# pi-zigbee-poe-rtc.net
KiCad netlist of a schematic drawn in EAGLE
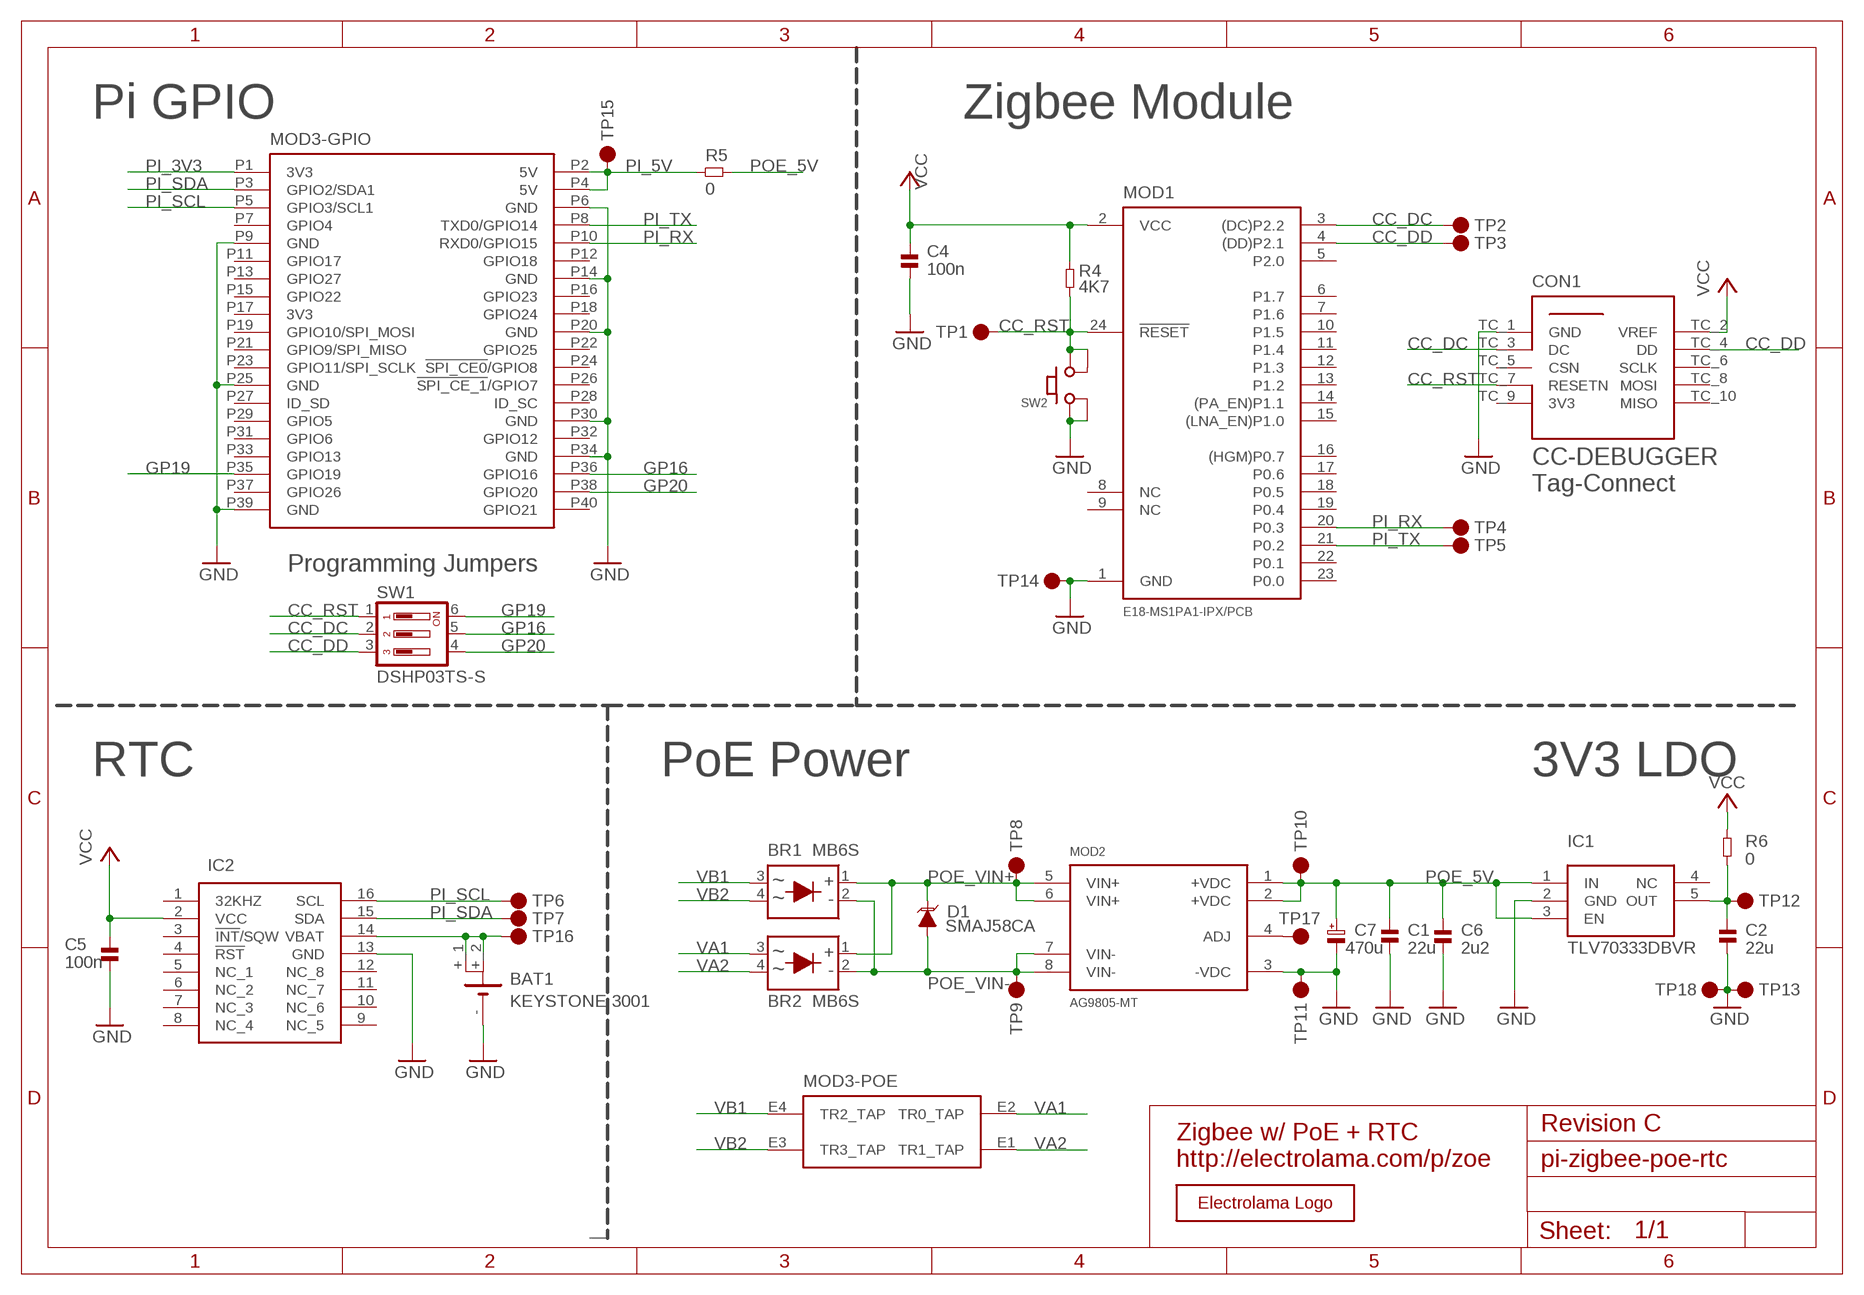
[diagram p0: schematic, sheet 1]

(export (version "E")
  (design (tool "Eeschema 10.0.6"))
  (components
    (comp (ref "BAT1")
      (value "KEYSTONE 3001")
      (footprint "eagle-import:KEYSTONE_3001")
      (libsource (lib "eagle-import") (part "BATTERY"))
    )
    (comp (ref "BR1")
      (value "MB6S")
      (footprint "eagle-import:SOP254P665X270-4N")
      (fields
        (field (name "MANUFACTURER_PART_NUMBER") "MB6S-TP")
        (field (name "MOUSER_PART_NUMBER") "833-MB6S-TP")
      )
      (libsource (lib "eagle-import") (part "DIODE-RECTIFIER-MB6S"))
    )
    (comp (ref "BR2")
      (value "MB6S")
      (footprint "eagle-import:SOP254P665X270-4N")
      (fields
        (field (name "MANUFACTURER_PART_NUMBER") "MB6S-TP")
        (field (name "MOUSER_PART_NUMBER") "833-MB6S-TP")
      )
      (libsource (lib "eagle-import") (part "DIODE-RECTIFIER-MB6S"))
    )
    (comp (ref "C1")
      (value "22u")
      (footprint "eagle-import:_PKG_C_0805")
      (libsource (lib "eagle-import") (part "CAP-0805"))
    )
    (comp (ref "C2")
      (value "22u")
      (footprint "eagle-import:_PKG_C_0805")
      (libsource (lib "eagle-import") (part "CAP-0805"))
    )
    (comp (ref "C4")
      (value "100n")
      (footprint "eagle-import:_PKG_C_0603")
      (libsource (lib "eagle-import") (part "CAP-0603"))
    )
    (comp (ref "C5")
      (value "100n")
      (footprint "eagle-import:_PKG_C_0603")
      (libsource (lib "eagle-import") (part "CAP-0603"))
    )
    (comp (ref "C6")
      (value "2u2")
      (footprint "eagle-import:_PKG_C_0603")
      (libsource (lib "eagle-import") (part "CAP-0603"))
    )
    (comp (ref "C7")
      (value "470u")
      (footprint "eagle-import:_CAP_ELCO_D8_L10.5")
      (libsource (lib "eagle-import") (part "CAP-POL-ELCO-D8-L10.5"))
    )
    (comp (ref "CON1")
      (value "TC2050-IDC-NL_CC-DEBUGGER")
      (footprint "eagle-import:TC2050-IDC-NL")
      (libsource (lib "eagle-import") (part "TC2050-IDC-NL_CC-DEBUGGER"))
    )
    (comp (ref "D1")
      (value "SMAJ58CA")
      (footprint "eagle-import:DIOM5126X250N-NOPOL")
      (libsource (lib "eagle-import") (part "DIODE-TVS-SMAJ58CA"))
    )
    (comp (ref "IC1")
      (value "TLV70333DBVR")
      (footprint "eagle-import:SOT95P280X145-5N")
      (fields (field (name "MOUSER_PART_NUMBER") "595-TLV70333DBVR"))
      (libsource (lib "eagle-import") (part "LDO-TLV70333DBVR"))
    )
    (comp (ref "IC2")
      (value "RTC-DS3231SN#")
      (footprint "eagle-import:SOIC127P1032X265-16N")
      (fields
        (field (name "MANUFACTURER_PART_NUMBER") "DS3231SN#")
        (field (name "MOUSER_PART_NUMBER") "700-DS3231SN#")
        (field (name "RS_PART_NUMBER") "1897251")
      )
      (libsource (lib "eagle-import") (part "RTC-DS3231SN#"))
    )
    (comp (ref "MOD1")
      (value "E18-MS1PA1-IPX/PCB")
      (footprint "eagle-import:EBYTE-E18-MS1PA1")
      (libsource (lib "eagle-import") (part "EBYTE-E18-MS1PA1"))
    )
    (comp (ref "MOD2")
      (value "AG9805-MT")
      (footprint "eagle-import:SILVERTEL_AG9800M")
      (libsource (lib "eagle-import") (part "SILVERTEL_AG9800M"))
    )
    (comp (ref "MOD3")
      (value "RPI-HAT-FULL")
      (footprint "eagle-import:RPI-HAT-FULL")
      (libsource (lib "eagle-import") (part "RPI-HAT-FULL"))
    )
    (comp (ref "R4")
      (value "4K7")
      (footprint "eagle-import:_PKG_C_0603")
      (libsource (lib "eagle-import") (part "RES-0603"))
    )
    (comp (ref "R5")
      (value "0")
      (footprint "eagle-import:TP_DUAL_1206")
      (libsource (lib "eagle-import") (part "TP_DUAL_1206"))
    )
    (comp (ref "R6")
      (value "0")
      (footprint "eagle-import:TP_DUAL_1206")
      (libsource (lib "eagle-import") (part "TP_DUAL_1206"))
    )
    (comp (ref "SW1")
      (value "DSHP03TS-S")
      (footprint "eagle-import:DSHP03TS-S")
      (libsource (lib "eagle-import") (part "SWITCH-DIP03-SMD"))
    )
    (comp (ref "SW2")
      (value "SPNO-XKB-TS-1187A")
      (footprint "eagle-import:XKB-TS-1187A")
      (libsource (lib "eagle-import") (part "SPNO-XKB-TS-1187A"))
    )
    (comp (ref "TP1")
      (value "TP")
      (footprint "eagle-import:TP_DOT")
      (libsource (lib "eagle-import") (part "TP"))
    )
    (comp (ref "TP2")
      (value "TP")
      (footprint "eagle-import:TP_DOT")
      (libsource (lib "eagle-import") (part "TP"))
    )
    (comp (ref "TP3")
      (value "TP")
      (footprint "eagle-import:TP_DOT")
      (libsource (lib "eagle-import") (part "TP"))
    )
    (comp (ref "TP4")
      (value "TP")
      (footprint "eagle-import:TP_DOT")
      (libsource (lib "eagle-import") (part "TP"))
    )
    (comp (ref "TP5")
      (value "TP")
      (footprint "eagle-import:TP_DOT")
      (libsource (lib "eagle-import") (part "TP"))
    )
    (comp (ref "TP6")
      (value "TP")
      (footprint "eagle-import:TP_DOT")
      (libsource (lib "eagle-import") (part "TP"))
    )
    (comp (ref "TP7")
      (value "TP")
      (footprint "eagle-import:TP_DOT")
      (libsource (lib "eagle-import") (part "TP"))
    )
    (comp (ref "TP8")
      (value "TP")
      (footprint "eagle-import:TP_DOT")
      (libsource (lib "eagle-import") (part "TP"))
    )
    (comp (ref "TP9")
      (value "TP")
      (footprint "eagle-import:TP_DOT")
      (libsource (lib "eagle-import") (part "TP"))
    )
    (comp (ref "TP10")
      (value "TP")
      (footprint "eagle-import:TP_DOT")
      (libsource (lib "eagle-import") (part "TP"))
    )
    (comp (ref "TP11")
      (value "TP")
      (footprint "eagle-import:TP_DOT")
      (libsource (lib "eagle-import") (part "TP"))
    )
    (comp (ref "TP12")
      (value "TP")
      (footprint "eagle-import:TP_DOT")
      (libsource (lib "eagle-import") (part "TP"))
    )
    (comp (ref "TP13")
      (value "TP")
      (footprint "eagle-import:TP_DOT")
      (libsource (lib "eagle-import") (part "TP"))
    )
    (comp (ref "TP14")
      (value "TP")
      (footprint "eagle-import:TP_DOT")
      (libsource (lib "eagle-import") (part "TP"))
    )
    (comp (ref "TP15")
      (value "TP")
      (footprint "eagle-import:TP_DOT")
      (libsource (lib "eagle-import") (part "TP"))
    )
    (comp (ref "TP16")
      (value "TP")
      (footprint "eagle-import:TP_DOT")
      (libsource (lib "eagle-import") (part "TP"))
    )
    (comp (ref "TP17")
      (value "TP")
      (footprint "eagle-import:TP_DOT")
      (libsource (lib "eagle-import") (part "TP"))
    )
    (comp (ref "TP18")
      (value "TP-HOOK")
      (footprint "eagle-import:TP_S2751-46R")
      (libsource (lib "eagle-import") (part "TP-HOOK"))
    )
    (comp (ref "U$1")
      (value "LOGO-ELECTROLAMA")
      (footprint "eagle-import:ELECTROLAMA")
      (libsource (lib "eagle-import") (part "LOGO-ELECTROLAMA"))
    )
  )
  (nets
    (net (code "1") (name "/CC_DC") (class "Default")
      (node (ref "CON1") (pin "TC_3") (pinfunction "DC_TC_3") (pintype "bidirectional"))
      (node (ref "MOD1") (pin "3") (pinfunction "(DC)P2.2_3") (pintype "bidirectional"))
      (node (ref "SW1") (pin "2") (pinfunction "2_2") (pintype "passive"))
      (node (ref "TP2") (pin "TP") (pinfunction "TP_TP") (pintype "bidirectional"))
    )
    (net (code "2") (name "/CC_DD") (class "Default")
      (node (ref "CON1") (pin "TC_4") (pinfunction "DD_TC_4") (pintype "bidirectional"))
      (node (ref "MOD1") (pin "4") (pinfunction "(DD)P2.1_4") (pintype "bidirectional"))
      (node (ref "SW1") (pin "3") (pinfunction "3_3") (pintype "passive"))
      (node (ref "TP3") (pin "TP") (pinfunction "TP_TP") (pintype "bidirectional"))
    )
    (net (code "3") (name "/CC_RST") (class "Default")
      (node (ref "CON1") (pin "TC_7") (pinfunction "RESETN_TC_7") (pintype "bidirectional"))
      (node (ref "MOD1") (pin "24") (pinfunction "~{RESET}_24") (pintype "input"))
      (node (ref "R4") (pin "1") (pinfunction "1_1") (pintype "passive"))
      (node (ref "SW1") (pin "1") (pinfunction "1_1") (pintype "passive"))
      (node (ref "SW2") (pin "C") (pinfunction "2_1_C") (pintype "bidirectional"))
      (node (ref "SW2") (pin "D") (pinfunction "2_2_D") (pintype "bidirectional"))
      (node (ref "TP1") (pin "TP") (pinfunction "TP_TP") (pintype "bidirectional"))
    )
    (net (code "4") (name "/GP16") (class "Default")
      (node (ref "MOD3") (pin "P36") (pinfunction "GPIO16_P36") (pintype "bidirectional"))
      (node (ref "SW1") (pin "5") (pinfunction "5_5") (pintype "passive"))
    )
    (net (code "5") (name "/GP19") (class "Default")
      (node (ref "MOD3") (pin "P35") (pinfunction "GPIO19_P35") (pintype "bidirectional"))
      (node (ref "SW1") (pin "6") (pinfunction "6_6") (pintype "passive"))
    )
    (net (code "6") (name "/GP20") (class "Default")
      (node (ref "MOD3") (pin "P38") (pinfunction "GPIO20_P38") (pintype "bidirectional"))
      (node (ref "SW1") (pin "4") (pinfunction "4_4") (pintype "passive"))
    )
    (net (code "7") (name "/PI_3V3") (class "Default")
      (node (ref "MOD3") (pin "P1") (pinfunction "3V3_P1") (pintype "bidirectional"))
    )
    (net (code "8") (name "/PI_5V") (class "Default")
      (node (ref "MOD3") (pin "P2") (pinfunction "5V_P2") (pintype "bidirectional"))
      (node (ref "MOD3") (pin "P4") (pinfunction "5V_P4") (pintype "bidirectional"))
      (node (ref "R5") (pin "1") (pinfunction "1_1") (pintype "passive"))
      (node (ref "TP15") (pin "TP") (pinfunction "TP_TP") (pintype "bidirectional"))
    )
    (net (code "9") (name "/PI_RX") (class "Default")
      (node (ref "MOD1") (pin "20") (pinfunction "P0.3_20") (pintype "bidirectional"))
      (node (ref "MOD3") (pin "P10") (pinfunction "RXD0/GPIO15_P10") (pintype "bidirectional"))
      (node (ref "TP4") (pin "TP") (pinfunction "TP_TP") (pintype "bidirectional"))
    )
    (net (code "10") (name "/PI_SCL") (class "Default")
      (node (ref "IC2") (pin "16") (pinfunction "SCL_16") (pintype "bidirectional"))
      (node (ref "MOD3") (pin "P5") (pinfunction "GPIO3/SCL1_P5") (pintype "bidirectional"))
      (node (ref "TP6") (pin "TP") (pinfunction "TP_TP") (pintype "bidirectional"))
    )
    (net (code "11") (name "/PI_SDA") (class "Default")
      (node (ref "IC2") (pin "15") (pinfunction "SDA_15") (pintype "bidirectional"))
      (node (ref "MOD3") (pin "P3") (pinfunction "GPIO2/SDA1_P3") (pintype "bidirectional"))
      (node (ref "TP7") (pin "TP") (pinfunction "TP_TP") (pintype "bidirectional"))
    )
    (net (code "12") (name "/PI_TX") (class "Default")
      (node (ref "MOD1") (pin "21") (pinfunction "P0.2_21") (pintype "bidirectional"))
      (node (ref "MOD3") (pin "P8") (pinfunction "TXD0/GPIO14_P8") (pintype "bidirectional"))
      (node (ref "TP5") (pin "TP") (pinfunction "TP_TP") (pintype "bidirectional"))
    )
    (net (code "13") (name "/POE_5V") (class "Default")
      (node (ref "C1") (pin "2") (pinfunction "2_2") (pintype "passive"))
      (node (ref "C6") (pin "1") (pinfunction "1_1") (pintype "passive"))
      (node (ref "C7") (pin "+") (pinfunction "+_+") (pintype "passive"))
      (node (ref "IC1") (pin "1") (pinfunction "IN_1") (pintype "bidirectional"))
      (node (ref "IC1") (pin "3") (pinfunction "EN_3") (pintype "bidirectional"))
      (node (ref "MOD2") (pin "1") (pinfunction "+VDC_1") (pintype "bidirectional"))
      (node (ref "MOD2") (pin "2") (pinfunction "+VDC_2") (pintype "bidirectional"))
      (node (ref "R5") (pin "2") (pinfunction "2_2") (pintype "passive"))
      (node (ref "TP10") (pin "TP") (pinfunction "TP_TP") (pintype "bidirectional"))
    )
    (net (code "14") (name "/POE_VIN+") (class "Default")
      (node (ref "BR1") (pin "1") (pinfunction "+_1") (pintype "bidirectional"))
      (node (ref "BR2") (pin "1") (pinfunction "+_1") (pintype "bidirectional"))
      (node (ref "D1") (pin "1") (pinfunction "C_1") (pintype "passive"))
      (node (ref "MOD2") (pin "5") (pinfunction "VIN+_5") (pintype "bidirectional"))
      (node (ref "MOD2") (pin "6") (pinfunction "VIN+_6") (pintype "bidirectional"))
      (node (ref "TP8") (pin "TP") (pinfunction "TP_TP") (pintype "bidirectional"))
    )
    (net (code "15") (name "/POE_VIN-") (class "Default")
      (node (ref "BR1") (pin "2") (pinfunction "-_2") (pintype "bidirectional"))
      (node (ref "BR2") (pin "2") (pinfunction "-_2") (pintype "bidirectional"))
      (node (ref "D1") (pin "2") (pinfunction "A_2") (pintype "passive"))
      (node (ref "MOD2") (pin "7") (pinfunction "VIN-_7") (pintype "bidirectional"))
      (node (ref "MOD2") (pin "8") (pinfunction "VIN-_8") (pintype "bidirectional"))
      (node (ref "TP9") (pin "TP") (pinfunction "TP_TP") (pintype "bidirectional"))
    )
    (net (code "16") (name "/VA1") (class "Default")
      (node (ref "BR2") (pin "3") (pinfunction "~_3") (pintype "bidirectional"))
      (node (ref "MOD3") (pin "E2") (pinfunction "TR0_TAP_E2") (pintype "bidirectional"))
    )
    (net (code "17") (name "/VA2") (class "Default")
      (node (ref "BR2") (pin "4") (pinfunction "~_4") (pintype "bidirectional"))
      (node (ref "MOD3") (pin "E1") (pinfunction "TR1_TAP_E1") (pintype "bidirectional"))
    )
    (net (code "18") (name "/VB1") (class "Default")
      (node (ref "BR1") (pin "3") (pinfunction "~_3") (pintype "bidirectional"))
      (node (ref "MOD3") (pin "E4") (pinfunction "TR2_TAP_E4") (pintype "bidirectional"))
    )
    (net (code "19") (name "/VB2") (class "Default")
      (node (ref "BR1") (pin "4") (pinfunction "~_4") (pintype "bidirectional"))
      (node (ref "MOD3") (pin "E3") (pinfunction "TR3_TAP_E3") (pintype "bidirectional"))
    )
    (net (code "20") (name "GND") (class "Default")
      (node (ref "BAT1") (pin "-") (pinfunction "-_-") (pintype "passive"))
      (node (ref "C1") (pin "1") (pinfunction "1_1") (pintype "passive"))
      (node (ref "C2") (pin "1") (pinfunction "1_1") (pintype "passive"))
      (node (ref "C4") (pin "2") (pinfunction "2_2") (pintype "passive"))
      (node (ref "C5") (pin "2") (pinfunction "2_2") (pintype "passive"))
      (node (ref "C6") (pin "2") (pinfunction "2_2") (pintype "passive"))
      (node (ref "C7") (pin "-") (pinfunction "-_-") (pintype "passive"))
      (node (ref "CON1") (pin "TC_1") (pinfunction "GND_TC_1") (pintype "bidirectional"))
      (node (ref "IC1") (pin "2") (pinfunction "GND_2") (pintype "bidirectional"))
      (node (ref "IC2") (pin "13") (pinfunction "GND_13") (pintype "power_in"))
      (node (ref "MOD1") (pin "1") (pinfunction "GND_1") (pintype "power_in"))
      (node (ref "MOD2") (pin "3") (pinfunction "-VDC_3") (pintype "bidirectional"))
      (node (ref "MOD3") (pin "P14") (pinfunction "GND_P14") (pintype "bidirectional"))
      (node (ref "MOD3") (pin "P20") (pinfunction "GND_P20") (pintype "bidirectional"))
      (node (ref "MOD3") (pin "P25") (pinfunction "GND_P25") (pintype "bidirectional"))
      (node (ref "MOD3") (pin "P30") (pinfunction "GND_P30") (pintype "bidirectional"))
      (node (ref "MOD3") (pin "P34") (pinfunction "GND_P34") (pintype "bidirectional"))
      (node (ref "MOD3") (pin "P39") (pinfunction "GND_P39") (pintype "bidirectional"))
      (node (ref "MOD3") (pin "P6") (pinfunction "GND_P6") (pintype "bidirectional"))
      (node (ref "MOD3") (pin "P9") (pinfunction "GND_P9") (pintype "bidirectional"))
      (node (ref "SW2") (pin "A") (pinfunction "1_1_A") (pintype "bidirectional"))
      (node (ref "SW2") (pin "B") (pinfunction "1_2_B") (pintype "bidirectional"))
      (node (ref "TP11") (pin "TP") (pinfunction "TP_TP") (pintype "bidirectional"))
      (node (ref "TP13") (pin "TP") (pinfunction "TP_TP") (pintype "bidirectional"))
      (node (ref "TP14") (pin "TP") (pinfunction "TP_TP") (pintype "bidirectional"))
      (node (ref "TP18") (pin "1") (pinfunction "TP_1") (pintype "bidirectional"))
    )
    (net (code "21") (name "Net-(BAT1-+1)") (class "Default")
      (node (ref "BAT1") (pin "+_1") (pinfunction "+1_+_1") (pintype "passive"))
      (node (ref "BAT1") (pin "+_2") (pinfunction "+2_+_2") (pintype "passive"))
      (node (ref "IC2") (pin "14") (pinfunction "VBAT_14") (pintype "bidirectional"))
      (node (ref "TP16") (pin "TP") (pinfunction "TP_TP") (pintype "bidirectional"))
    )
    (net (code "22") (name "Net-(IC1-OUT)") (class "Default")
      (node (ref "C2") (pin "2") (pinfunction "2_2") (pintype "passive"))
      (node (ref "IC1") (pin "5") (pinfunction "OUT_5") (pintype "bidirectional"))
      (node (ref "R6") (pin "1") (pinfunction "1_1") (pintype "passive"))
      (node (ref "TP12") (pin "TP") (pinfunction "TP_TP") (pintype "bidirectional"))
    )
    (net (code "23") (name "Net-(MOD2-ADJ)") (class "Default")
      (node (ref "MOD2") (pin "4") (pinfunction "ADJ_4") (pintype "bidirectional"))
      (node (ref "TP17") (pin "TP") (pinfunction "TP_TP") (pintype "bidirectional"))
    )
    (net (code "24") (name "VCC") (class "Default")
      (node (ref "C4") (pin "1") (pinfunction "1_1") (pintype "passive"))
      (node (ref "C5") (pin "1") (pinfunction "1_1") (pintype "passive"))
      (node (ref "CON1") (pin "TC_2") (pinfunction "VREF_TC_2") (pintype "bidirectional"))
      (node (ref "IC2") (pin "2") (pinfunction "VCC_2") (pintype "power_in"))
      (node (ref "MOD1") (pin "2") (pinfunction "VCC_2") (pintype "power_in"))
      (node (ref "R4") (pin "2") (pinfunction "2_2") (pintype "passive"))
      (node (ref "R6") (pin "2") (pinfunction "2_2") (pintype "passive"))
    )
    (net (code "25") (name "unconnected-(CON1-3V3-PadTC_9)") (class "Default")
      (node (ref "CON1") (pin "TC_9") (pinfunction "3V3_TC_9") (pintype "bidirectional"))
    )
    (net (code "26") (name "unconnected-(CON1-CSN-PadTC_5)") (class "Default")
      (node (ref "CON1") (pin "TC_5") (pinfunction "CSN_TC_5") (pintype "bidirectional"))
    )
    (net (code "27") (name "unconnected-(CON1-MISO-PadTC_10)") (class "Default")
      (node (ref "CON1") (pin "TC_10") (pinfunction "MISO_TC_10") (pintype "bidirectional"))
    )
    (net (code "28") (name "unconnected-(CON1-MOSI-PadTC_8)") (class "Default")
      (node (ref "CON1") (pin "TC_8") (pinfunction "MOSI_TC_8") (pintype "bidirectional"))
    )
    (net (code "29") (name "unconnected-(CON1-SCLK-PadTC_6)") (class "Default")
      (node (ref "CON1") (pin "TC_6") (pinfunction "SCLK_TC_6") (pintype "bidirectional"))
    )
    (net (code "30") (name "unconnected-(IC1-NC-Pad4)") (class "Default")
      (node (ref "IC1") (pin "4") (pinfunction "NC_4") (pintype "no_connect"))
    )
    (net (code "31") (name "unconnected-(IC2-32KHZ-Pad1)") (class "Default")
      (node (ref "IC2") (pin "1") (pinfunction "32KHZ_1") (pintype "bidirectional"))
    )
    (net (code "32") (name "unconnected-(IC2-NC_1-Pad5)") (class "Default")
      (node (ref "IC2") (pin "5") (pinfunction "NC_1_5") (pintype "bidirectional"))
    )
    (net (code "33") (name "unconnected-(IC2-NC_2-Pad6)") (class "Default")
      (node (ref "IC2") (pin "6") (pinfunction "NC_2_6") (pintype "bidirectional"))
    )
    (net (code "34") (name "unconnected-(IC2-NC_3-Pad7)") (class "Default")
      (node (ref "IC2") (pin "7") (pinfunction "NC_3_7") (pintype "bidirectional"))
    )
    (net (code "35") (name "unconnected-(IC2-NC_4-Pad8)") (class "Default")
      (node (ref "IC2") (pin "8") (pinfunction "NC_4_8") (pintype "bidirectional"))
    )
    (net (code "36") (name "unconnected-(IC2-NC_5-Pad9)") (class "Default")
      (node (ref "IC2") (pin "9") (pinfunction "NC_5_9") (pintype "bidirectional"))
    )
    (net (code "37") (name "unconnected-(IC2-NC_6-Pad10)") (class "Default")
      (node (ref "IC2") (pin "10") (pinfunction "NC_6_10") (pintype "bidirectional"))
    )
    (net (code "38") (name "unconnected-(IC2-NC_7-Pad11)") (class "Default")
      (node (ref "IC2") (pin "11") (pinfunction "NC_7_11") (pintype "bidirectional"))
    )
    (net (code "39") (name "unconnected-(IC2-NC_8-Pad12)") (class "Default")
      (node (ref "IC2") (pin "12") (pinfunction "NC_8_12") (pintype "bidirectional"))
    )
    (net (code "40") (name "unconnected-(IC2-~{INT}{slash}SQW-Pad3)") (class "Default")
      (node (ref "IC2") (pin "3") (pinfunction "~{INT}/SQW_3") (pintype "input"))
    )
    (net (code "41") (name "unconnected-(IC2-~{RST}-Pad4)") (class "Default")
      (node (ref "IC2") (pin "4") (pinfunction "~{RST}_4") (pintype "input"))
    )
    (net (code "42") (name "unconnected-(MOD1-(HGM)P0.7-Pad16)") (class "Default")
      (node (ref "MOD1") (pin "16") (pinfunction "(HGM)P0.7_16") (pintype "output"))
    )
    (net (code "43") (name "unconnected-(MOD1-(LNA_EN)P1.0-Pad15)") (class "Default")
      (node (ref "MOD1") (pin "15") (pinfunction "(LNA_EN)P1.0_15") (pintype "output"))
    )
    (net (code "44") (name "unconnected-(MOD1-(PA_EN)P1.1-Pad14)") (class "Default")
      (node (ref "MOD1") (pin "14") (pinfunction "(PA_EN)P1.1_14") (pintype "output"))
    )
    (net (code "45") (name "unconnected-(MOD1-NC-Pad8)") (class "Default")
      (node (ref "MOD1") (pin "8") (pinfunction "NC_8") (pintype "no_connect"))
    )
    (net (code "46") (name "unconnected-(MOD1-NC-Pad9)") (class "Default")
      (node (ref "MOD1") (pin "9") (pinfunction "NC_9") (pintype "no_connect"))
    )
    (net (code "47") (name "unconnected-(MOD1-P0.0-Pad23)") (class "Default")
      (node (ref "MOD1") (pin "23") (pinfunction "P0.0_23") (pintype "bidirectional"))
    )
    (net (code "48") (name "unconnected-(MOD1-P0.1-Pad22)") (class "Default")
      (node (ref "MOD1") (pin "22") (pinfunction "P0.1_22") (pintype "bidirectional"))
    )
    (net (code "49") (name "unconnected-(MOD1-P0.4-Pad19)") (class "Default")
      (node (ref "MOD1") (pin "19") (pinfunction "P0.4_19") (pintype "bidirectional"))
    )
    (net (code "50") (name "unconnected-(MOD1-P0.5-Pad18)") (class "Default")
      (node (ref "MOD1") (pin "18") (pinfunction "P0.5_18") (pintype "bidirectional"))
    )
    (net (code "51") (name "unconnected-(MOD1-P0.6-Pad17)") (class "Default")
      (node (ref "MOD1") (pin "17") (pinfunction "P0.6_17") (pintype "bidirectional"))
    )
    (net (code "52") (name "unconnected-(MOD1-P1.2-Pad13)") (class "Default")
      (node (ref "MOD1") (pin "13") (pinfunction "P1.2_13") (pintype "bidirectional"))
    )
    (net (code "53") (name "unconnected-(MOD1-P1.3-Pad12)") (class "Default")
      (node (ref "MOD1") (pin "12") (pinfunction "P1.3_12") (pintype "bidirectional"))
    )
    (net (code "54") (name "unconnected-(MOD1-P1.4-Pad11)") (class "Default")
      (node (ref "MOD1") (pin "11") (pinfunction "P1.4_11") (pintype "bidirectional"))
    )
    (net (code "55") (name "unconnected-(MOD1-P1.5-Pad10)") (class "Default")
      (node (ref "MOD1") (pin "10") (pinfunction "P1.5_10") (pintype "bidirectional"))
    )
    (net (code "56") (name "unconnected-(MOD1-P1.6-Pad7)") (class "Default")
      (node (ref "MOD1") (pin "7") (pinfunction "P1.6_7") (pintype "bidirectional"))
    )
    (net (code "57") (name "unconnected-(MOD1-P1.7-Pad6)") (class "Default")
      (node (ref "MOD1") (pin "6") (pinfunction "P1.7_6") (pintype "bidirectional"))
    )
    (net (code "58") (name "unconnected-(MOD1-P2.0-Pad5)") (class "Default")
      (node (ref "MOD1") (pin "5") (pinfunction "P2.0_5") (pintype "bidirectional"))
    )
    (net (code "59") (name "unconnected-(MOD3A-3V3-PadP17)") (class "Default")
      (node (ref "MOD3") (pin "P17") (pinfunction "3V3_P17") (pintype "bidirectional"))
    )
    (net (code "60") (name "unconnected-(MOD3A-GPIO4-PadP7)") (class "Default")
      (node (ref "MOD3") (pin "P7") (pinfunction "GPIO4_P7") (pintype "bidirectional"))
    )
    (net (code "61") (name "unconnected-(MOD3A-GPIO5-PadP29)") (class "Default")
      (node (ref "MOD3") (pin "P29") (pinfunction "GPIO5_P29") (pintype "bidirectional"))
    )
    (net (code "62") (name "unconnected-(MOD3A-GPIO6-PadP31)") (class "Default")
      (node (ref "MOD3") (pin "P31") (pinfunction "GPIO6_P31") (pintype "bidirectional"))
    )
    (net (code "63") (name "unconnected-(MOD3A-GPIO9{slash}SPI_MISO-PadP21)") (class "Default")
      (node (ref "MOD3") (pin "P21") (pinfunction "GPIO9/SPI_MISO_P21") (pintype "bidirectional"))
    )
    (net (code "64") (name "unconnected-(MOD3A-GPIO10{slash}SPI_MOSI-PadP19)") (class "Default")
      (node (ref "MOD3") (pin "P19") (pinfunction "GPIO10/SPI_MOSI_P19") (pintype "bidirectional"))
    )
    (net (code "65") (name "unconnected-(MOD3A-GPIO11{slash}SPI_SCLK-PadP23)") (class "Default")
      (node (ref "MOD3") (pin "P23") (pinfunction "GPIO11/SPI_SCLK_P23") (pintype "bidirectional"))
    )
    (net (code "66") (name "unconnected-(MOD3A-GPIO12-PadP32)") (class "Default")
      (node (ref "MOD3") (pin "P32") (pinfunction "GPIO12_P32") (pintype "bidirectional"))
    )
    (net (code "67") (name "unconnected-(MOD3A-GPIO13-PadP33)") (class "Default")
      (node (ref "MOD3") (pin "P33") (pinfunction "GPIO13_P33") (pintype "bidirectional"))
    )
    (net (code "68") (name "unconnected-(MOD3A-GPIO17-PadP11)") (class "Default")
      (node (ref "MOD3") (pin "P11") (pinfunction "GPIO17_P11") (pintype "bidirectional"))
    )
    (net (code "69") (name "unconnected-(MOD3A-GPIO18-PadP12)") (class "Default")
      (node (ref "MOD3") (pin "P12") (pinfunction "GPIO18_P12") (pintype "bidirectional"))
    )
    (net (code "70") (name "unconnected-(MOD3A-GPIO21-PadP40)") (class "Default")
      (node (ref "MOD3") (pin "P40") (pinfunction "GPIO21_P40") (pintype "bidirectional"))
    )
    (net (code "71") (name "unconnected-(MOD3A-GPIO22-PadP15)") (class "Default")
      (node (ref "MOD3") (pin "P15") (pinfunction "GPIO22_P15") (pintype "bidirectional"))
    )
    (net (code "72") (name "unconnected-(MOD3A-GPIO23-PadP16)") (class "Default")
      (node (ref "MOD3") (pin "P16") (pinfunction "GPIO23_P16") (pintype "bidirectional"))
    )
    (net (code "73") (name "unconnected-(MOD3A-GPIO24-PadP18)") (class "Default")
      (node (ref "MOD3") (pin "P18") (pinfunction "GPIO24_P18") (pintype "bidirectional"))
    )
    (net (code "74") (name "unconnected-(MOD3A-GPIO25-PadP22)") (class "Default")
      (node (ref "MOD3") (pin "P22") (pinfunction "GPIO25_P22") (pintype "bidirectional"))
    )
    (net (code "75") (name "unconnected-(MOD3A-GPIO26-PadP37)") (class "Default")
      (node (ref "MOD3") (pin "P37") (pinfunction "GPIO26_P37") (pintype "bidirectional"))
    )
    (net (code "76") (name "unconnected-(MOD3A-GPIO27-PadP13)") (class "Default")
      (node (ref "MOD3") (pin "P13") (pinfunction "GPIO27_P13") (pintype "bidirectional"))
    )
    (net (code "77") (name "unconnected-(MOD3A-ID_SC-PadP28)") (class "Default")
      (node (ref "MOD3") (pin "P28") (pinfunction "ID_SC_P28") (pintype "bidirectional"))
    )
    (net (code "78") (name "unconnected-(MOD3A-ID_SD-PadP27)") (class "Default")
      (node (ref "MOD3") (pin "P27") (pinfunction "ID_SD_P27") (pintype "bidirectional"))
    )
    (net (code "79") (name "unconnected-(MOD3A-~{SPI_CE0}{slash}GPIO8-PadP24)") (class "Default")
      (node (ref "MOD3") (pin "P24") (pinfunction "~{SPI_CE0}/GPIO8_P24") (pintype "bidirectional"))
    )
    (net (code "80") (name "unconnected-(MOD3A-~{SPI_CE_1}{slash}GPIO7-PadP26)") (class "Default")
      (node (ref "MOD3") (pin "P26") (pinfunction "~{SPI_CE_1}/GPIO7_P26") (pintype "bidirectional"))
    )
  )
)
